# Buck.net
KiCad netlist of a schematic drawn in Altium Designer
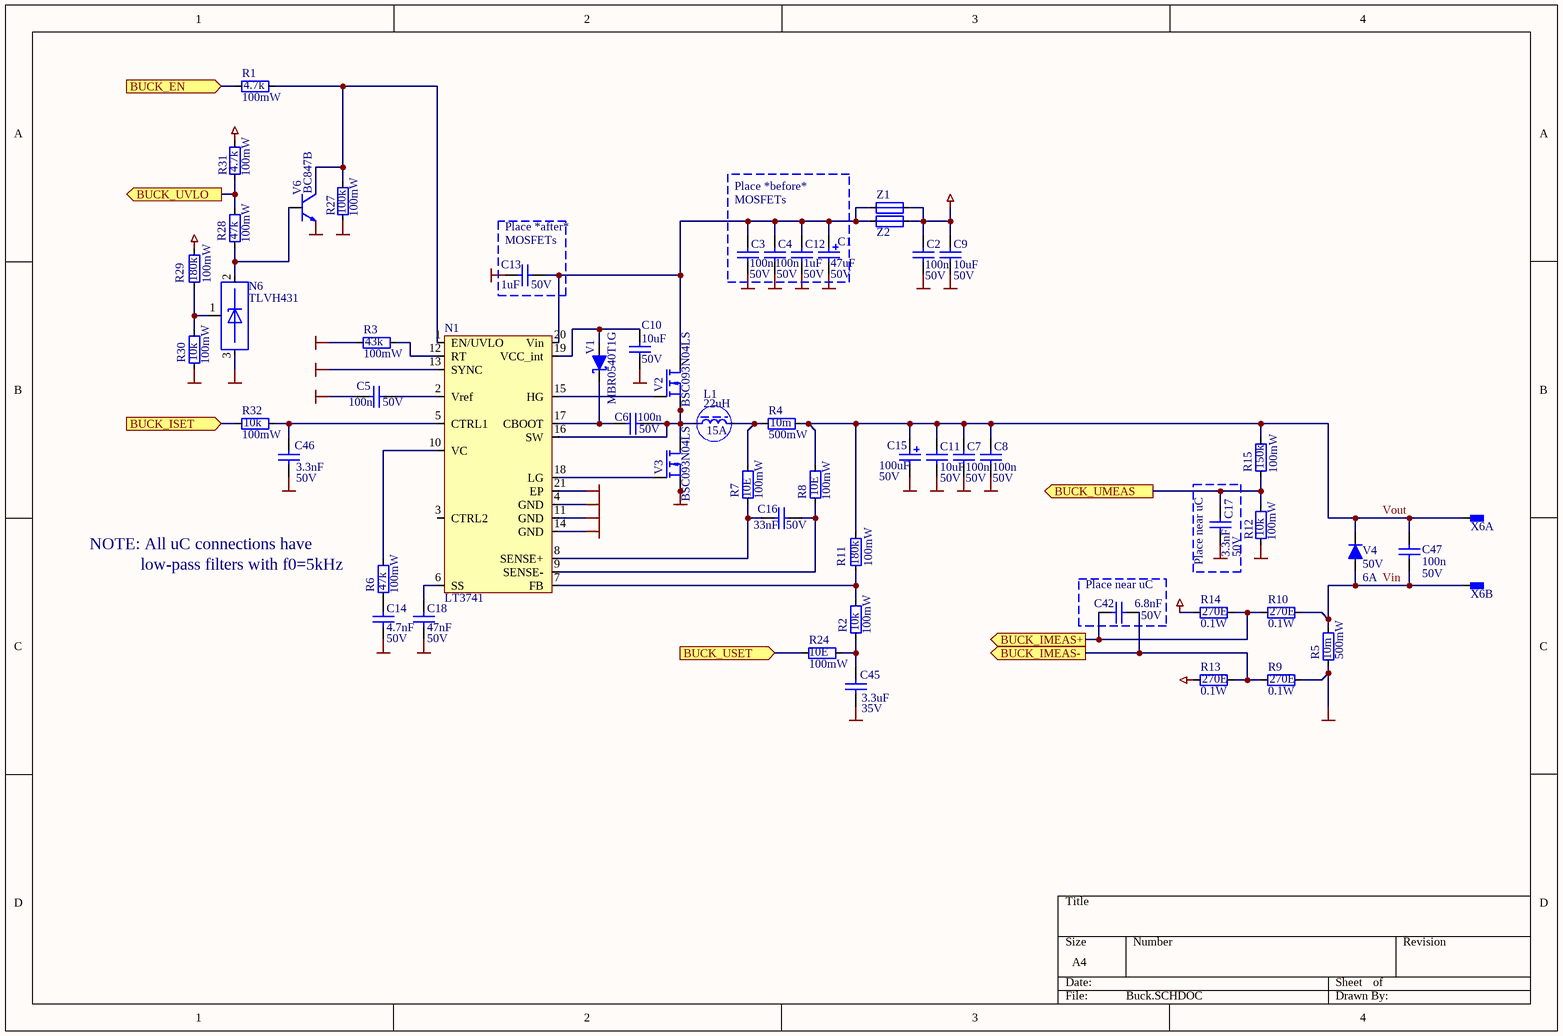
[diagram p0: Buck.SCHDOC]

(export (version "E")
  (design (tool "Eeschema 10.0.6"))
  (components
    (comp (ref "C1")
      (value "C_SMD_ALU_47U_50V_20%_PCV1H470MCL7GS")
      (footprint "SMD_CAP_CV_8x10L")
      (fields (field (name "ALTIUM_VALUE") "47uF") (field (name "VALUE2") "50V"))
      (libsource (lib "C-Capacitor") (part "C_SMD_ALU_47U_50V_20%_PCV1H470MCL7GS"))
    )
    (comp (ref "C2")
      (value "C_SMD_CER_100N_50V_10%_X7R_0603")
      (footprint "SMD_0603")
      (description "SMD Capacitor")
      (fields (field (name "ALTIUM_VALUE") "100n") (field (name "VALUE2") "50V"))
      (libsource (lib "C-Capacitor") (part "C_SMD_CER_100N_50V_10%_X7R_0603"))
    )
    (comp (ref "C3")
      (value "C_SMD_CER_100N_50V_10%_X7R_0603")
      (footprint "SMD_0603")
      (description "SMD Capacitor")
      (fields (field (name "ALTIUM_VALUE") "100n") (field (name "VALUE2") "50V"))
      (libsource (lib "C-Capacitor") (part "C_SMD_CER_100N_50V_10%_X7R_0603"))
    )
    (comp (ref "C4")
      (value "C_SMD_CER_100N_50V_10%_X7R_0603")
      (footprint "SMD_0603")
      (description "SMD Capacitor")
      (fields (field (name "ALTIUM_VALUE") "100n") (field (name "VALUE2") "50V"))
      (libsource (lib "C-Capacitor") (part "C_SMD_CER_100N_50V_10%_X7R_0603"))
    )
    (comp (ref "C5")
      (value "C_SMD_CER_100N_50V_10%_X7R_0603")
      (footprint "SMD_0603")
      (description "SMD Capacitor")
      (fields (field (name "ALTIUM_VALUE") "100n") (field (name "VALUE2") "50V"))
      (libsource (lib "C-Capacitor") (part "C_SMD_CER_100N_50V_10%_X7R_0603"))
    )
    (comp (ref "C6")
      (value "C_SMD_CER_100N_50V_10%_X7R_0603")
      (footprint "SMD_0603")
      (description "SMD Capacitor")
      (fields (field (name "ALTIUM_VALUE") "100n") (field (name "VALUE2") "50V"))
      (libsource (lib "C-Capacitor") (part "C_SMD_CER_100N_50V_10%_X7R_0603"))
    )
    (comp (ref "C7")
      (value "C_SMD_CER_100N_50V_10%_X7R_0603")
      (footprint "SMD_0603")
      (description "SMD Capacitor")
      (fields (field (name "ALTIUM_VALUE") "100n") (field (name "VALUE2") "50V"))
      (libsource (lib "C-Capacitor") (part "C_SMD_CER_100N_50V_10%_X7R_0603"))
    )
    (comp (ref "C8")
      (value "C_SMD_CER_100N_50V_10%_X7R_0603")
      (footprint "SMD_0603")
      (description "SMD Capacitor")
      (fields (field (name "ALTIUM_VALUE") "100n") (field (name "VALUE2") "50V"))
      (libsource (lib "C-Capacitor") (part "C_SMD_CER_100N_50V_10%_X7R_0603"))
    )
    (comp (ref "C9")
      (value "C_SMD_CER_10U_50V_10%_X7R_1210")
      (footprint "SMD_1210")
      (description "SMD Ceramic capacitor")
      (fields (field (name "ALTIUM_VALUE") "10uF") (field (name "VALUE2") "50V"))
      (libsource (lib "AM") (part "C_SMD_CER_10U_50V_10%_X7R_1210"))
    )
    (comp (ref "C10")
      (value "C_SMD_CER_10U_50V_10%_X7R_1210")
      (footprint "SMD_1210")
      (description "SMD Ceramic capacitor")
      (fields (field (name "ALTIUM_VALUE") "10uF") (field (name "VALUE2") "50V"))
      (libsource (lib "AM") (part "C_SMD_CER_10U_50V_10%_X7R_1210"))
    )
    (comp (ref "C11")
      (value "C_SMD_CER_10U_50V_10%_X7R_1210")
      (footprint "SMD_1210")
      (description "SMD Ceramic capacitor")
      (fields (field (name "ALTIUM_VALUE") "10uF") (field (name "VALUE2") "50V"))
      (libsource (lib "AM") (part "C_SMD_CER_10U_50V_10%_X7R_1210"))
    )
    (comp (ref "C12")
      (value "C_SMD_CER_1U_50V_10%_X7R_0805")
      (footprint "SMD_0805")
      (fields (field (name "ALTIUM_VALUE") "1uF") (field (name "VALUE2") "50V"))
      (libsource (lib "AM") (part "C_SMD_CER_1U_50V_10%_X7R_0805"))
    )
    (comp (ref "C13")
      (value "C_SMD_CER_1U_50V_10%_X7R_0805")
      (footprint "SMD_0805")
      (fields (field (name "ALTIUM_VALUE") "1uF") (field (name "VALUE2") "50V"))
      (libsource (lib "AM") (part "C_SMD_CER_1U_50V_10%_X7R_0805"))
    )
    (comp (ref "C14")
      (value "C_SMD_CER_4N7_50V_10%_X7R_0603")
      (footprint "SMD_0603")
      (description "SMD Capacitor ceramic")
      (fields (field (name "ALTIUM_VALUE") "4.7nF") (field (name "VALUE2") "50V"))
      (libsource (lib "C-Capacitor") (part "C_SMD_CER_4N7_50V_10%_X7R_0603"))
    )
    (comp (ref "C15")
      (value "C_SMD_ALU_100U_50V_20%_PCV1H101MCL2GS")
      (footprint "SMD_CAP_CV_10x12.7L")
      (fields (field (name "ALTIUM_VALUE") "100uF") (field (name "VALUE2") "50V"))
      (libsource (lib "AM") (part "C_SMD_ALU_100U_50V_20%_PCV1H101MCL2GS"))
    )
    (comp (ref "C16")
      (value "C_SMD_CER_33N_50V_10%_X7R_0603")
      (footprint "SMD_0603")
      (fields (field (name "ALTIUM_VALUE") "33nF") (field (name "VALUE2") "50V"))
      (libsource (lib "AM") (part "C_SMD_CER_33N_50V_10%_X7R_0603"))
    )
    (comp (ref "C17")
      (value "C_SMD_CER_3N3_50V_10%_X7R_0603")
      (footprint "SMD_0603")
      (description "Thinfilm Ceramic Capacitor")
      (fields (field (name "ALTIUM_VALUE") "3.3nF") (field (name "VALUE2") "50V"))
      (libsource (lib "AM") (part "C_SMD_CER_3N3_50V_10%_X7R_0603"))
    )
    (comp (ref "C18")
      (value "C_SMD_CER_47N_50V_10%_X7R_0603")
      (footprint "SMD_0603")
      (description "SMD capacitor")
      (fields (field (name "ALTIUM_VALUE") "47nF") (field (name "VALUE2") "50V"))
      (libsource (lib "C-Capacitor") (part "C_SMD_CER_47N_50V_10%_X7R_0603"))
    )
    (comp (ref "C42")
      (value "C_SMD_CER_6N8_50V_10%_X7R_0603")
      (footprint "SMD_0603")
      (fields (field (name "ALTIUM_VALUE") "6.8nF") (field (name "VALUE2") "50V"))
      (libsource (lib "AM") (part "C_SMD_CER_6N8_50V_10%_X7R_0603"))
    )
    (comp (ref "C45")
      (value "C_SMD_CER_3U3_35V_10%_X7R_0805")
      (footprint "SMD_0805")
      (fields (field (name "ALTIUM_VALUE") "3.3uF") (field (name "VALUE2") "35V"))
      (libsource (lib "AM") (part "C_SMD_CER_3U3_35V_10%_X7R_0805"))
    )
    (comp (ref "C46")
      (value "C_SMD_CER_3N3_50V_10%_X7R_0603")
      (footprint "SMD_0603")
      (description "Thinfilm Ceramic Capacitor")
      (fields (field (name "ALTIUM_VALUE") "3.3nF") (field (name "VALUE2") "50V"))
      (libsource (lib "AM") (part "C_SMD_CER_3N3_50V_10%_X7R_0603"))
    )
    (comp (ref "C47")
      (value "C_SMD_CER_100N_50V_10%_X7R_0603")
      (footprint "SMD_0603")
      (description "SMD Capacitor")
      (fields (field (name "ALTIUM_VALUE") "100n") (field (name "VALUE2") "50V"))
      (libsource (lib "C-Capacitor") (part "C_SMD_CER_100N_50V_10%_X7R_0603"))
    )
    (comp (ref "L1")
      (value "L_SMD_22U_15A_7MOHM_20%_74435582200")
      (footprint "SMD_INDUCT-74435582200")
      (fields (field (name "ALTIUM_VALUE") "22uH") (field (name "VALUE2") "15A"))
      (libsource (lib "AM") (part "L_SMD_22U_15A_7MOHM_20%_74435582200"))
    )
    (comp (ref "N1")
      (value "N_LT3741EUF_QFN-20")
      (footprint "SMD_QFN-20")
      (description "High Power, CCVC, Step-Down Controller")
      (fields (field (name "TYPE") "LT3741"))
      (libsource (lib "N-Analog") (part "N_LT3741EUF_QFN-20"))
    )
    (comp (ref "N6")
      (value "N_TLVH431_SOT23-3")
      (footprint "SMD_SOT_23_3")
      (description "LOW-VOLTAGE ADJUSTABLE PRECISION SHUNT REGULATORS")
      (fields (field (name "TYPE") "TLVH431"))
      (libsource (lib "AM") (part "N_TLVH431_SOT23-3"))
    )
    (comp (ref "R1")
      (value "R_SMD_THINFILM_4K7_0W1_1%_50PPM_0603")
      (footprint "SMD_0603")
      (description "SMD Resistor")
      (fields (field (name "ALTIUM_VALUE") "4.7k") (field (name "VALUE2") "100mW"))
      (libsource (lib "R-Resistor") (part "R_SMD_THINFILM_4K7_0W1_1%_50PPM_0603"))
    )
    (comp (ref "R2")
      (value "R_SMD_THINFILM_10K_0W1_1%_50PPM_0603")
      (footprint "SMD_0603")
      (description "SMD Resistor")
      (fields (field (name "ALTIUM_VALUE") "10k") (field (name "VALUE2") "100mW"))
      (libsource (lib "R-Resistor") (part "R_SMD_THINFILM_10K_0W1_1%_50PPM_0603"))
    )
    (comp (ref "R3")
      (value "R_SMD_THINFILM_43K_0W1_0.1%_25PPM_0603")
      (footprint "SMD_0603")
      (description "SMD Resistor")
      (fields (field (name "ALTIUM_VALUE") "43k") (field (name "VALUE2") "100mW"))
      (libsource (lib "AM") (part "R_SMD_THINFILM_43K_0W1_0.1%_25PPM_0603"))
    )
    (comp (ref "R4")
      (value "R_SMD_THICKFILM_0E01_0W5_0.5%_50PPM_1206")
      (footprint "SMD_1206")
      (description "SMD Current sense resistor")
      (fields (field (name "ALTIUM_VALUE") "10m") (field (name "VALUE2") "500mW"))
      (libsource (lib "AM") (part "R_SMD_THICKFILM_0E01_0W5_0.5%_50PPM_1206"))
    )
    (comp (ref "R5")
      (value "R_SMD_THICKFILM_0E01_0W5_0.5%_50PPM_1206")
      (footprint "SMD_1206")
      (description "SMD Current sense resistor")
      (fields (field (name "ALTIUM_VALUE") "10m") (field (name "VALUE2") "500mW"))
      (libsource (lib "AM") (part "R_SMD_THICKFILM_0E01_0W5_0.5%_50PPM_1206"))
    )
    (comp (ref "R6")
      (value "R_SMD_THINFILM_47K_0W1_1%_50PPM_0603")
      (footprint "SMD_0603")
      (description "SMD Resistor")
      (fields (field (name "ALTIUM_VALUE") "47k") (field (name "VALUE2") "100mW"))
      (libsource (lib "R-Resistor") (part "R_SMD_THINFILM_47K_0W1_1%_50PPM_0603"))
    )
    (comp (ref "R7")
      (value "R_SMD_THINFILM_10E_0W1_1%_50PPM_0603")
      (footprint "SMD_0603")
      (description "SMD Resistor")
      (fields (field (name "ALTIUM_VALUE") "10E") (field (name "VALUE2") "100mW"))
      (libsource (lib "R-Resistor") (part "R_SMD_THINFILM_10E_0W1_1%_50PPM_0603"))
    )
    (comp (ref "R8")
      (value "R_SMD_THINFILM_10E_0W1_1%_50PPM_0603")
      (footprint "SMD_0603")
      (description "SMD Resistor")
      (fields (field (name "ALTIUM_VALUE") "10E") (field (name "VALUE2") "100mW"))
      (libsource (lib "R-Resistor") (part "R_SMD_THINFILM_10E_0W1_1%_50PPM_0603"))
    )
    (comp (ref "R9")
      (value "R_SMD_THINFILM_270E_0W1_1%_50PPM_0603")
      (footprint "SMD_0603")
      (description "SMD Resistor")
      (fields (field (name "ALTIUM_VALUE") "270E") (field (name "VALUE2") "0.1W"))
      (libsource (lib "AM") (part "R_SMD_THINFILM_270E_0W1_1%_50PPM_0603"))
    )
    (comp (ref "R10")
      (value "R_SMD_THINFILM_270E_0W1_1%_50PPM_0603")
      (footprint "SMD_0603")
      (description "SMD Resistor")
      (fields (field (name "ALTIUM_VALUE") "270E") (field (name "VALUE2") "0.1W"))
      (libsource (lib "AM") (part "R_SMD_THINFILM_270E_0W1_1%_50PPM_0603"))
    )
    (comp (ref "R11")
      (value "R_SMD_THINFILM_180K_0W1_0.1%_25PPM_0603")
      (footprint "SMD_0603")
      (description "SMD Resistor")
      (fields (field (name "ALTIUM_VALUE") "180k") (field (name "VALUE2") "100mW"))
      (libsource (lib "AM") (part "R_SMD_THINFILM_180K_0W1_0.1%_25PPM_0603"))
    )
    (comp (ref "R12")
      (value "R_SMD_THINFILM_10K_0W1_1%_50PPM_0603")
      (footprint "SMD_0603")
      (description "SMD Resistor")
      (fields (field (name "ALTIUM_VALUE") "10k") (field (name "VALUE2") "100mW"))
      (libsource (lib "R-Resistor") (part "R_SMD_THINFILM_10K_0W1_1%_50PPM_0603"))
    )
    (comp (ref "R13")
      (value "R_SMD_THINFILM_270E_0W1_1%_50PPM_0603")
      (footprint "SMD_0603")
      (description "SMD Resistor")
      (fields (field (name "ALTIUM_VALUE") "270E") (field (name "VALUE2") "0.1W"))
      (libsource (lib "AM") (part "R_SMD_THINFILM_270E_0W1_1%_50PPM_0603"))
    )
    (comp (ref "R14")
      (value "R_SMD_THINFILM_270E_0W1_1%_50PPM_0603")
      (footprint "SMD_0603")
      (description "SMD Resistor")
      (fields (field (name "ALTIUM_VALUE") "270E") (field (name "VALUE2") "0.1W"))
      (libsource (lib "AM") (part "R_SMD_THINFILM_270E_0W1_1%_50PPM_0603"))
    )
    (comp (ref "R15")
      (value "R_SMD_THINFILM_150K_0W1_1%_50PPM_0603")
      (footprint "SMD_0603")
      (description "SMD Resistor")
      (fields (field (name "ALTIUM_VALUE") "150k") (field (name "VALUE2") "100mW"))
      (libsource (lib "R-Resistor") (part "R_SMD_THINFILM_150K_0W1_1%_50PPM_0603"))
    )
    (comp (ref "R24")
      (value "R_SMD_THINFILM_10E_0W1_1%_50PPM_0603")
      (footprint "SMD_0603")
      (description "SMD Resistor")
      (fields (field (name "ALTIUM_VALUE") "10E") (field (name "VALUE2") "100mW"))
      (libsource (lib "R-Resistor") (part "R_SMD_THINFILM_10E_0W1_1%_50PPM_0603"))
    )
    (comp (ref "R27")
      (value "R_SMD_THINFILM_100K_0W1_1%_50PPM_0603")
      (footprint "SMD_0603")
      (description "SMD Resistor")
      (fields (field (name "ALTIUM_VALUE") "100k") (field (name "VALUE2") "100mW"))
      (libsource (lib "R-Resistor") (part "R_SMD_THINFILM_100K_0W1_1%_50PPM_0603"))
    )
    (comp (ref "R28")
      (value "R_SMD_THINFILM_47K_0W1_1%_50PPM_0603")
      (footprint "SMD_0603")
      (description "SMD Resistor")
      (fields (field (name "ALTIUM_VALUE") "47k") (field (name "VALUE2") "100mW"))
      (libsource (lib "R-Resistor") (part "R_SMD_THINFILM_47K_0W1_1%_50PPM_0603"))
    )
    (comp (ref "R29")
      (value "R_SMD_THINFILM_180K_0W1_0.1%_25PPM_0603")
      (footprint "SMD_0603")
      (description "SMD Resistor")
      (fields (field (name "ALTIUM_VALUE") "180k") (field (name "VALUE2") "100mW"))
      (libsource (lib "AM") (part "R_SMD_THINFILM_180K_0W1_0.1%_25PPM_0603"))
    )
    (comp (ref "R30")
      (value "R_SMD_THINFILM_10K_0W1_1%_50PPM_0603")
      (footprint "SMD_0603")
      (description "SMD Resistor")
      (fields (field (name "ALTIUM_VALUE") "10k") (field (name "VALUE2") "100mW"))
      (libsource (lib "R-Resistor") (part "R_SMD_THINFILM_10K_0W1_1%_50PPM_0603"))
    )
    (comp (ref "R31")
      (value "R_SMD_THINFILM_4K7_0W1_1%_50PPM_0603")
      (footprint "SMD_0603")
      (description "SMD Resistor")
      (fields (field (name "ALTIUM_VALUE") "4.7k") (field (name "VALUE2") "100mW"))
      (libsource (lib "R-Resistor") (part "R_SMD_THINFILM_4K7_0W1_1%_50PPM_0603"))
    )
    (comp (ref "R32")
      (value "R_SMD_THINFILM_10K_0W1_1%_50PPM_0603")
      (footprint "SMD_0603")
      (description "SMD Resistor")
      (fields (field (name "ALTIUM_VALUE") "10k") (field (name "VALUE2") "100mW"))
      (libsource (lib "R-Resistor") (part "R_SMD_THINFILM_10K_0W1_1%_50PPM_0603"))
    )
    (comp (ref "V1")
      (value "V_SMD_SCHOTTKY_MBR0540T1G_40V_0A5_SOD-123")
      (footprint "SMD_SOD_123")
      (description "Schottky diode, 40V, 500mA, SOD-123")
      (fields (field (name "TYPE") "MBR0540T1G"))
      (libsource (lib "AM") (part "V_SMD_SCHOTTKY_MBR0540T1G_40V_0A5_SOD-123"))
    )
    (comp (ref "V2")
      (value "V_SMD_FET_NMOS_BSC093N04LS_40V_13A_24NC_0E0093_PG-TDSON-8")
      (footprint "SMD_PG-TDSON-8")
      (description "Fast switching mosfet for SMPS")
      (fields (field (name "TYPE") "BSC093N04LS"))
      (libsource (lib "V-Semiconductors") (part "V_SMD_FET_NMOS_BSC093N04LS_40V_13A_24NC_0E0093_PG-TDSON-8"))
    )
    (comp (ref "V3")
      (value "V_SMD_FET_NMOS_BSC093N04LS_40V_13A_24NC_0E0093_PG-TDSON-8")
      (footprint "SMD_PG-TDSON-8")
      (description "Fast switching mosfet for SMPS")
      (fields (field (name "TYPE") "BSC093N04LS"))
      (libsource (lib "V-Semiconductors") (part "V_SMD_FET_NMOS_BSC093N04LS_40V_13A_24NC_0E0093_PG-TDSON-8"))
    )
    (comp (ref "V4")
      (value "V_THT_DIODE_6A05-T_50V_6A")
      (footprint "THT_6A05-T_2")
      (description "6A05-T")
      (fields (field (name "ALTIUM_VALUE") "50V") (field (name "VALUE2") "6A"))
      (libsource (lib "V-Semiconductors") (part "V_THT_DIODE_6A05-T_50V_6A"))
    )
    (comp (ref "V6")
      (value "V_SMD_TRANS_NPN_BC847B_50V_0A2_SOT-23-3")
      (footprint "SMD_SOT_23_3")
      (description "NPN Transistor")
      (fields (field (name "TYPE") "BC847B"))
      (libsource (lib "V-Semiconductors") (part "V_SMD_TRANS_NPN_BC847B_50V_0A2_SOT-23-3"))
    )
    (comp (ref "X6")
      (value "X_CONNECTOR_P2.54_D0.9_1X2")
      (footprint "THT_CON_P2.54_D0.9_1X2")
      (description "Pitch 2.54, Diameter 0.9mm, 1 row, 2 columns")
      (libsource (lib "AM") (part "X_CONNECTOR_P2.54_D0.9_1X2"))
    )
    (comp (ref "Z1")
      (value "Z_SMD_FERRITE_5A_60E@100MHZ_0805")
      (footprint "SMD_0805")
      (description "BEAD FERRITE 60 OHM 5A")
      (libsource (lib "AM") (part "Z_SMD_FERRITE_5A_60E@100MHZ_0805"))
    )
    (comp (ref "Z2")
      (value "Z_SMD_FERRITE_5A_60E@100MHZ_0805")
      (footprint "SMD_0805")
      (description "BEAD FERRITE 60 OHM 5A")
      (libsource (lib "AM") (part "Z_SMD_FERRITE_5A_60E@100MHZ_0805"))
    )
  )
  (nets
    (net (code "1") (name "+3.3V") (class "Default")
      (node (ref "R13") (pin "2") (pinfunction "2_2") (pintype "passive"))
      (node (ref "R14") (pin "2") (pinfunction "2_2") (pintype "passive"))
      (node (ref "R31") (pin "2") (pinfunction "2_2") (pintype "passive"))
    )
    (net (code "2") (name "+36V") (class "Default")
      (node (ref "C2") (pin "2") (pinfunction "2_2") (pintype "passive"))
      (node (ref "C9") (pin "2") (pinfunction "2_2") (pintype "passive"))
      (node (ref "R29") (pin "2") (pinfunction "2_2") (pintype "passive"))
      (node (ref "Z1") (pin "2") (pinfunction "2_2") (pintype "passive"))
      (node (ref "Z2") (pin "2") (pinfunction "2_2") (pintype "passive"))
    )
    (net (code "3") (name "/BUCK_EN") (class "Default")
      (node (ref "R1") (pin "1") (pinfunction "1_1") (pintype "passive"))
    )
    (net (code "4") (name "/BUCK_IMEAS+") (class "Default")
      (node (ref "C42") (pin "1") (pinfunction "1_1") (pintype "passive"))
      (node (ref "R10") (pin "2") (pinfunction "2_2") (pintype "passive"))
      (node (ref "R14") (pin "1") (pinfunction "1_1") (pintype "passive"))
    )
    (net (code "5") (name "/BUCK_IMEAS-") (class "Default")
      (node (ref "C42") (pin "2") (pinfunction "2_2") (pintype "passive"))
      (node (ref "R13") (pin "1") (pinfunction "1_1") (pintype "passive"))
      (node (ref "R9") (pin "2") (pinfunction "2_2") (pintype "passive"))
    )
    (net (code "6") (name "/BUCK_ISET") (class "Default")
      (node (ref "R32") (pin "1") (pinfunction "1_1") (pintype "passive"))
    )
    (net (code "7") (name "/BUCK_UMEAS") (class "Default")
      (node (ref "C17") (pin "2") (pinfunction "2_2") (pintype "passive"))
      (node (ref "R12") (pin "2") (pinfunction "2_2") (pintype "passive"))
      (node (ref "R15") (pin "1") (pinfunction "1_1") (pintype "passive"))
    )
    (net (code "8") (name "/BUCK_USET") (class "Default")
      (node (ref "R24") (pin "1") (pinfunction "1_1") (pintype "passive"))
    )
    (net (code "9") (name "/BUCK_UVLO") (class "Default")
      (node (ref "R28") (pin "2") (pinfunction "2_2") (pintype "passive"))
      (node (ref "R31") (pin "1") (pinfunction "1_1") (pintype "passive"))
    )
    (net (code "10") (name "/Vin") (class "Default")
      (node (ref "C47") (pin "1") (pinfunction "1_1") (pintype "passive"))
      (node (ref "R10") (pin "1") (pinfunction "1_1") (pintype "passive"))
      (node (ref "R5") (pin "2") (pinfunction "2_2") (pintype "passive"))
      (node (ref "V4") (pin "1") (pinfunction "1_1") (pintype "passive"))
      (node (ref "X6") (pin "2") (pinfunction "2_2") (pintype "passive"))
    )
    (net (code "11") (name "/Vout") (class "Default")
      (node (ref "C11") (pin "2") (pinfunction "2_2") (pintype "passive"))
      (node (ref "C15") (pin "2") (pinfunction "2_2") (pintype "passive"))
      (node (ref "C47") (pin "2") (pinfunction "2_2") (pintype "passive"))
      (node (ref "C7") (pin "2") (pinfunction "2_2") (pintype "passive"))
      (node (ref "C8") (pin "2") (pinfunction "2_2") (pintype "passive"))
      (node (ref "R11") (pin "2") (pinfunction "2_2") (pintype "passive"))
      (node (ref "R15") (pin "2") (pinfunction "2_2") (pintype "passive"))
      (node (ref "R4") (pin "2") (pinfunction "2_2") (pintype "passive"))
      (node (ref "R8") (pin "2") (pinfunction "2_2") (pintype "passive"))
      (node (ref "V4") (pin "2") (pinfunction "2_2") (pintype "passive"))
      (node (ref "X6") (pin "1") (pinfunction "1_1") (pintype "passive"))
    )
    (net (code "12") (name "GND") (class "Default")
      (node (ref "C1") (pin "1") (pinfunction "1_1") (pintype "passive"))
      (node (ref "C10") (pin "2") (pinfunction "2_2") (pintype "passive"))
      (node (ref "C11") (pin "1") (pinfunction "1_1") (pintype "passive"))
      (node (ref "C12") (pin "1") (pinfunction "1_1") (pintype "passive"))
      (node (ref "C13") (pin "2") (pinfunction "2_2") (pintype "passive"))
      (node (ref "C14") (pin "1") (pinfunction "1_1") (pintype "passive"))
      (node (ref "C15") (pin "1") (pinfunction "1_1") (pintype "passive"))
      (node (ref "C17") (pin "1") (pinfunction "1_1") (pintype "passive"))
      (node (ref "C18") (pin "1") (pinfunction "1_1") (pintype "passive"))
      (node (ref "C2") (pin "1") (pinfunction "1_1") (pintype "passive"))
      (node (ref "C3") (pin "1") (pinfunction "1_1") (pintype "passive"))
      (node (ref "C4") (pin "1") (pinfunction "1_1") (pintype "passive"))
      (node (ref "C45") (pin "1") (pinfunction "1_1") (pintype "passive"))
      (node (ref "C46") (pin "1") (pinfunction "1_1") (pintype "passive"))
      (node (ref "C5") (pin "2") (pinfunction "2_2") (pintype "passive"))
      (node (ref "C7") (pin "1") (pinfunction "1_1") (pintype "passive"))
      (node (ref "C8") (pin "1") (pinfunction "1_1") (pintype "passive"))
      (node (ref "C9") (pin "1") (pinfunction "1_1") (pintype "passive"))
      (node (ref "N1") (pin "11") (pinfunction "GND_11") (pintype "passive"))
      (node (ref "N1") (pin "13") (pinfunction "SYNC_13") (pintype "passive"))
      (node (ref "N1") (pin "14") (pinfunction "GND_14") (pintype "passive"))
      (node (ref "N1") (pin "21") (pinfunction "EP_21") (pintype "passive"))
      (node (ref "N1") (pin "4") (pinfunction "GND_4") (pintype "passive"))
      (node (ref "N6") (pin "3") (pinfunction "3_3") (pintype "passive"))
      (node (ref "R12") (pin "1") (pinfunction "1_1") (pintype "passive"))
      (node (ref "R27") (pin "1") (pinfunction "1_1") (pintype "passive"))
      (node (ref "R3") (pin "1") (pinfunction "1_1") (pintype "passive"))
      (node (ref "R30") (pin "1") (pinfunction "1_1") (pintype "passive"))
      (node (ref "R5") (pin "1") (pinfunction "1_1") (pintype "passive"))
      (node (ref "R9") (pin "1") (pinfunction "1_1") (pintype "passive"))
      (node (ref "V3") (pin "1") (pinfunction "Source1_1") (pintype "passive"))
      (node (ref "V3") (pin "2") (pinfunction "Source2_2") (pintype "passive"))
      (node (ref "V3") (pin "3") (pinfunction "Source3_3") (pintype "passive"))
      (node (ref "V6") (pin "2") (pinfunction "E_2") (pintype "passive"))
    )
    (net (code "13") (name "Net-(C14-Pad2)") (class "Default")
      (node (ref "C14") (pin "2") (pinfunction "2_2") (pintype "passive"))
      (node (ref "R6") (pin "1") (pinfunction "1_1") (pintype "passive"))
    )
    (net (code "14") (name "Net-(C45-Pad2)") (class "Default")
      (node (ref "C45") (pin "2") (pinfunction "2_2") (pintype "passive"))
      (node (ref "R2") (pin "2") (pinfunction "2_2") (pintype "passive"))
      (node (ref "R24") (pin "2") (pinfunction "2_2") (pintype "passive"))
    )
    (net (code "15") (name "Net-(L1-Pad2)") (class "Default")
      (node (ref "L1") (pin "2") (pinfunction "2_2") (pintype "passive"))
      (node (ref "R4") (pin "1") (pinfunction "1_1") (pintype "passive"))
      (node (ref "R7") (pin "2") (pinfunction "2_2") (pintype "passive"))
    )
    (net (code "16") (name "Net-(N1-CBOOT)") (class "Default")
      (node (ref "C6") (pin "1") (pinfunction "1_1") (pintype "passive"))
      (node (ref "N1") (pin "17") (pinfunction "CBOOT_17") (pintype "passive"))
      (node (ref "V1") (pin "2") (pinfunction "2_2") (pintype "passive"))
    )
    (net (code "17") (name "Net-(N1-CTRL1)") (class "Default")
      (node (ref "C46") (pin "2") (pinfunction "2_2") (pintype "passive"))
      (node (ref "N1") (pin "5") (pinfunction "CTRL1_5") (pintype "passive"))
      (node (ref "R32") (pin "2") (pinfunction "2_2") (pintype "passive"))
    )
    (net (code "18") (name "Net-(N1-EN{slash}UVLO)") (class "Default")
      (node (ref "N1") (pin "1") (pinfunction "EN/UVLO_1") (pintype "passive"))
      (node (ref "R1") (pin "2") (pinfunction "2_2") (pintype "passive"))
      (node (ref "R27") (pin "2") (pinfunction "2_2") (pintype "passive"))
      (node (ref "V6") (pin "3") (pinfunction "C_3") (pintype "passive"))
    )
    (net (code "19") (name "Net-(N1-FB)") (class "Default")
      (node (ref "N1") (pin "7") (pinfunction "FB_7") (pintype "passive"))
      (node (ref "R11") (pin "1") (pinfunction "1_1") (pintype "passive"))
      (node (ref "R2") (pin "1") (pinfunction "1_1") (pintype "passive"))
    )
    (net (code "20") (name "Net-(N1-HG)") (class "Default")
      (node (ref "N1") (pin "15") (pinfunction "HG_15") (pintype "passive"))
      (node (ref "V2") (pin "4") (pinfunction "Gate_4") (pintype "passive"))
    )
    (net (code "21") (name "Net-(N1-LG)") (class "Default")
      (node (ref "N1") (pin "18") (pinfunction "LG_18") (pintype "passive"))
      (node (ref "V3") (pin "4") (pinfunction "Gate_4") (pintype "passive"))
    )
    (net (code "22") (name "Net-(N1-RT)") (class "Default")
      (node (ref "N1") (pin "12") (pinfunction "RT_12") (pintype "passive"))
      (node (ref "R3") (pin "2") (pinfunction "2_2") (pintype "passive"))
    )
    (net (code "23") (name "Net-(N1-SENSE+)") (class "Default")
      (node (ref "C16") (pin "2") (pinfunction "2_2") (pintype "passive"))
      (node (ref "N1") (pin "8") (pinfunction "SENSE+_8") (pintype "passive"))
      (node (ref "R7") (pin "1") (pinfunction "1_1") (pintype "passive"))
    )
    (net (code "24") (name "Net-(N1-SENSE-)") (class "Default")
      (node (ref "C16") (pin "1") (pinfunction "1_1") (pintype "passive"))
      (node (ref "N1") (pin "9") (pinfunction "SENSE-_9") (pintype "passive"))
      (node (ref "R8") (pin "1") (pinfunction "1_1") (pintype "passive"))
    )
    (net (code "25") (name "Net-(N1-SS)") (class "Default")
      (node (ref "C18") (pin "2") (pinfunction "2_2") (pintype "passive"))
      (node (ref "N1") (pin "6") (pinfunction "SS_6") (pintype "passive"))
    )
    (net (code "26") (name "Net-(N1-SW)") (class "Default")
      (node (ref "C6") (pin "2") (pinfunction "2_2") (pintype "passive"))
      (node (ref "L1") (pin "1") (pinfunction "1_1") (pintype "passive"))
      (node (ref "N1") (pin "16") (pinfunction "SW_16") (pintype "passive"))
      (node (ref "V2") (pin "1") (pinfunction "Source1_1") (pintype "passive"))
      (node (ref "V2") (pin "2") (pinfunction "Source2_2") (pintype "passive"))
      (node (ref "V2") (pin "3") (pinfunction "Source3_3") (pintype "passive"))
      (node (ref "V3") (pin "5") (pinfunction "Drain_5") (pintype "passive"))
    )
    (net (code "27") (name "Net-(N1-VC)") (class "Default")
      (node (ref "N1") (pin "10") (pinfunction "VC_10") (pintype "passive"))
      (node (ref "R6") (pin "2") (pinfunction "2_2") (pintype "passive"))
    )
    (net (code "28") (name "Net-(N1-VCC_int)") (class "Default")
      (node (ref "C10") (pin "1") (pinfunction "1_1") (pintype "passive"))
      (node (ref "N1") (pin "19") (pinfunction "VCC_int_19") (pintype "passive"))
      (node (ref "V1") (pin "1") (pinfunction "1_1") (pintype "passive"))
    )
    (net (code "29") (name "Net-(N1-Vin)") (class "Default")
      (node (ref "C1") (pin "2") (pinfunction "2_2") (pintype "passive"))
      (node (ref "C12") (pin "2") (pinfunction "2_2") (pintype "passive"))
      (node (ref "C13") (pin "1") (pinfunction "1_1") (pintype "passive"))
      (node (ref "C3") (pin "2") (pinfunction "2_2") (pintype "passive"))
      (node (ref "C4") (pin "2") (pinfunction "2_2") (pintype "passive"))
      (node (ref "N1") (pin "20") (pinfunction "Vin_20") (pintype "passive"))
      (node (ref "V2") (pin "5") (pinfunction "Drain_5") (pintype "passive"))
      (node (ref "Z1") (pin "1") (pinfunction "1_1") (pintype "passive"))
      (node (ref "Z2") (pin "1") (pinfunction "1_1") (pintype "passive"))
    )
    (net (code "30") (name "Net-(N1-Vref)") (class "Default")
      (node (ref "C5") (pin "1") (pinfunction "1_1") (pintype "passive"))
      (node (ref "N1") (pin "2") (pinfunction "Vref_2") (pintype "passive"))
    )
    (net (code "31") (name "Net-(N6-Pad1)") (class "Default")
      (node (ref "N6") (pin "1") (pinfunction "1_1") (pintype "passive"))
      (node (ref "R29") (pin "1") (pinfunction "1_1") (pintype "passive"))
      (node (ref "R30") (pin "2") (pinfunction "2_2") (pintype "passive"))
    )
    (net (code "32") (name "Net-(V6-B)") (class "Default")
      (node (ref "N6") (pin "2") (pinfunction "2_2") (pintype "passive"))
      (node (ref "R28") (pin "1") (pinfunction "1_1") (pintype "passive"))
      (node (ref "V6") (pin "1") (pinfunction "B_1") (pintype "passive"))
    )
    (net (code "33") (name "unconnected-(N1-CTRL2-Pad3)") (class "Default")
      (node (ref "N1") (pin "3") (pinfunction "CTRL2_3") (pintype "passive"))
    )
  )
)
